# panel.net
KiCad netlist of a schematic drawn in EAGLE
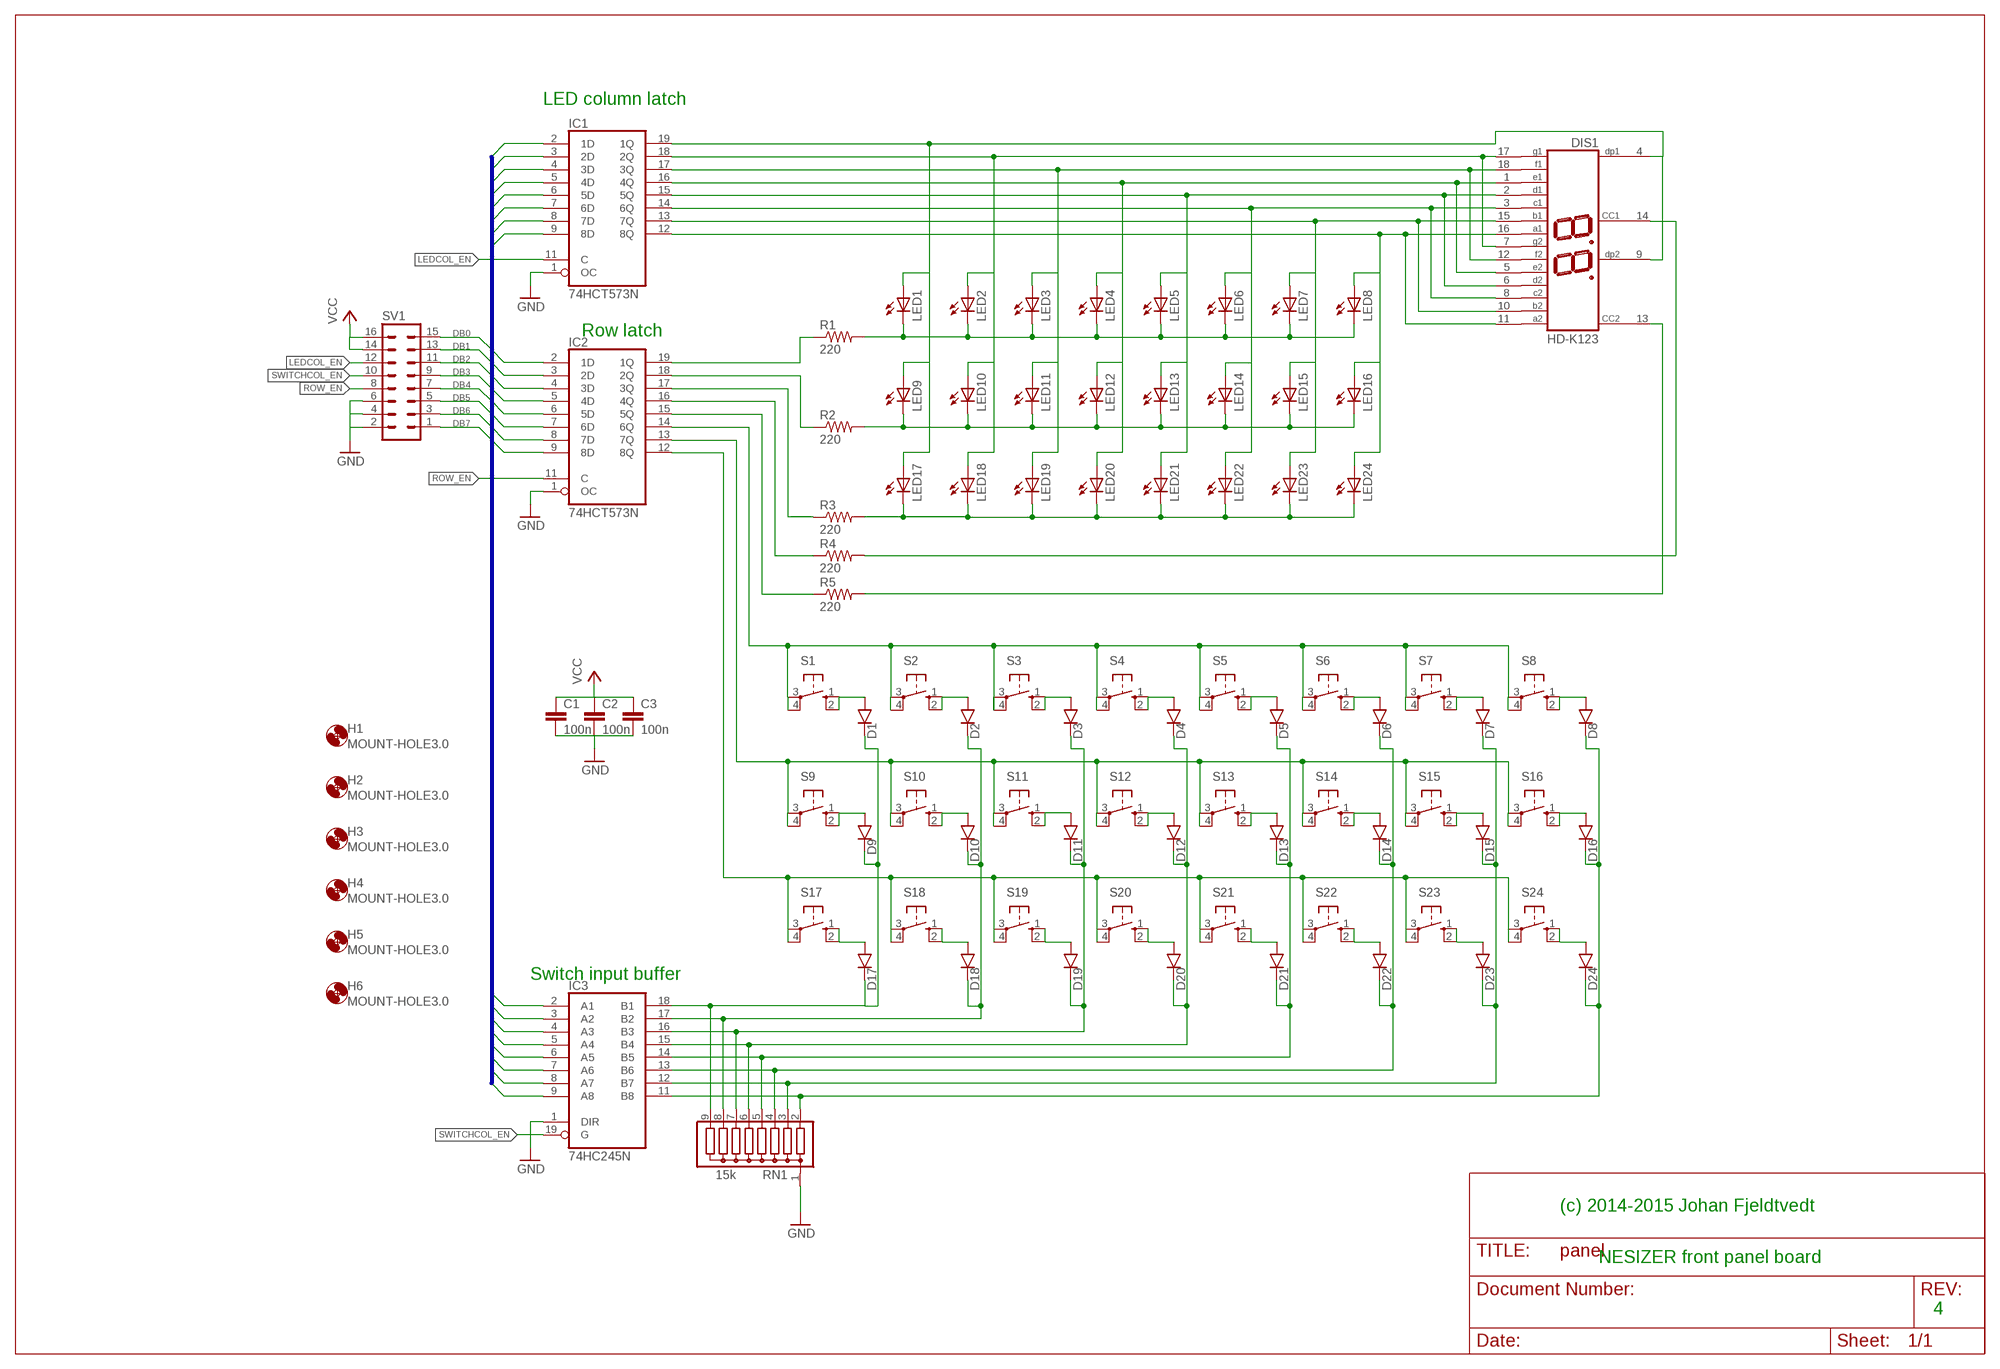
[diagram p0: schematic, sheet 1]

(export (version "E")
  (design (tool "Eeschema 10.0.6"))
  (components
    (comp (ref "C1")
      (value "100n")
      (footprint "eagle-import:C025-025X050")
      (libsource (lib "eagle-import") (part "C-EU025-025X050"))
    )
    (comp (ref "C2")
      (value "100n")
      (footprint "eagle-import:C025-025X050")
      (libsource (lib "eagle-import") (part "C-EU025-025X050"))
    )
    (comp (ref "C3")
      (value "100n")
      (footprint "eagle-import:C025-025X050")
      (libsource (lib "eagle-import") (part "C-EU025-025X050"))
    )
    (comp (ref "D1")
      (value "1N914.3")
      (footprint "eagle-import:DO35-3")
      (libsource (lib "eagle-import") (part "1N914.3"))
    )
    (comp (ref "D2")
      (value "1N914.3")
      (footprint "eagle-import:DO35-3")
      (libsource (lib "eagle-import") (part "1N914.3"))
    )
    (comp (ref "D3")
      (value "1N914.3")
      (footprint "eagle-import:DO35-3")
      (libsource (lib "eagle-import") (part "1N914.3"))
    )
    (comp (ref "D4")
      (value "1N914.3")
      (footprint "eagle-import:DO35-3")
      (libsource (lib "eagle-import") (part "1N914.3"))
    )
    (comp (ref "D5")
      (value "1N914.3")
      (footprint "eagle-import:DO35-3")
      (libsource (lib "eagle-import") (part "1N914.3"))
    )
    (comp (ref "D6")
      (value "1N914.3")
      (footprint "eagle-import:DO35-3")
      (libsource (lib "eagle-import") (part "1N914.3"))
    )
    (comp (ref "D7")
      (value "1N914.3")
      (footprint "eagle-import:DO35-3")
      (libsource (lib "eagle-import") (part "1N914.3"))
    )
    (comp (ref "D8")
      (value "1N914.3")
      (footprint "eagle-import:DO35-3")
      (libsource (lib "eagle-import") (part "1N914.3"))
    )
    (comp (ref "D9")
      (value "1N914.3")
      (footprint "eagle-import:DO35-3")
      (libsource (lib "eagle-import") (part "1N914.3"))
    )
    (comp (ref "D10")
      (value "1N914.3")
      (footprint "eagle-import:DO35-3")
      (libsource (lib "eagle-import") (part "1N914.3"))
    )
    (comp (ref "D11")
      (value "1N914.3")
      (footprint "eagle-import:DO35-3")
      (libsource (lib "eagle-import") (part "1N914.3"))
    )
    (comp (ref "D12")
      (value "1N914.3")
      (footprint "eagle-import:DO35-3")
      (libsource (lib "eagle-import") (part "1N914.3"))
    )
    (comp (ref "D13")
      (value "1N914.3")
      (footprint "eagle-import:DO35-3")
      (libsource (lib "eagle-import") (part "1N914.3"))
    )
    (comp (ref "D14")
      (value "1N914.3")
      (footprint "eagle-import:DO35-3")
      (libsource (lib "eagle-import") (part "1N914.3"))
    )
    (comp (ref "D15")
      (value "1N914.3")
      (footprint "eagle-import:DO35-3")
      (libsource (lib "eagle-import") (part "1N914.3"))
    )
    (comp (ref "D16")
      (value "1N914.3")
      (footprint "eagle-import:DO35-3")
      (libsource (lib "eagle-import") (part "1N914.3"))
    )
    (comp (ref "D17")
      (value "1N914.3")
      (footprint "eagle-import:DO35-3")
      (libsource (lib "eagle-import") (part "1N914.3"))
    )
    (comp (ref "D18")
      (value "1N914.3")
      (footprint "eagle-import:DO35-3")
      (libsource (lib "eagle-import") (part "1N914.3"))
    )
    (comp (ref "D19")
      (value "1N914.3")
      (footprint "eagle-import:DO35-3")
      (libsource (lib "eagle-import") (part "1N914.3"))
    )
    (comp (ref "D20")
      (value "1N914.3")
      (footprint "eagle-import:DO35-3")
      (libsource (lib "eagle-import") (part "1N914.3"))
    )
    (comp (ref "D21")
      (value "1N914.3")
      (footprint "eagle-import:DO35-3")
      (libsource (lib "eagle-import") (part "1N914.3"))
    )
    (comp (ref "D22")
      (value "1N914.3")
      (footprint "eagle-import:DO35-3")
      (libsource (lib "eagle-import") (part "1N914.3"))
    )
    (comp (ref "D23")
      (value "1N914.3")
      (footprint "eagle-import:DO35-3")
      (libsource (lib "eagle-import") (part "1N914.3"))
    )
    (comp (ref "D24")
      (value "1N914.3")
      (footprint "eagle-import:DO35-3")
      (libsource (lib "eagle-import") (part "1N914.3"))
    )
    (comp (ref "DIS1")
      (value "HD-K123")
      (footprint "eagle-import:HDSP-R")
      (libsource (lib "eagle-import") (part "HD-K123"))
    )
    (comp (ref "H1")
      (value "MOUNT-HOLE3.0")
      (footprint "eagle-import:3,0")
      (libsource (lib "eagle-import") (part "MOUNT-HOLE3.0"))
    )
    (comp (ref "H2")
      (value "MOUNT-HOLE3.0")
      (footprint "eagle-import:3,0")
      (libsource (lib "eagle-import") (part "MOUNT-HOLE3.0"))
    )
    (comp (ref "H3")
      (value "MOUNT-HOLE3.0")
      (footprint "eagle-import:3,0")
      (libsource (lib "eagle-import") (part "MOUNT-HOLE3.0"))
    )
    (comp (ref "H4")
      (value "MOUNT-HOLE3.0")
      (footprint "eagle-import:3,0")
      (libsource (lib "eagle-import") (part "MOUNT-HOLE3.0"))
    )
    (comp (ref "H5")
      (value "MOUNT-HOLE3.0")
      (footprint "eagle-import:3,0")
      (libsource (lib "eagle-import") (part "MOUNT-HOLE3.0"))
    )
    (comp (ref "H6")
      (value "MOUNT-HOLE3.0")
      (footprint "eagle-import:3,0")
      (libsource (lib "eagle-import") (part "MOUNT-HOLE3.0"))
    )
    (comp (ref "IC1")
      (value "74HCT573N")
      (footprint "eagle-import:DIL20")
      (libsource (lib "eagle-import") (part "74573NHCT"))
    )
    (comp (ref "IC2")
      (value "74HCT573N")
      (footprint "eagle-import:DIL20")
      (libsource (lib "eagle-import") (part "74573NHCT"))
    )
    (comp (ref "IC3")
      (value "74HC245N")
      (footprint "eagle-import:DIL20")
      (libsource (lib "eagle-import") (part "74245NHC"))
    )
    (comp (ref "LED1")
      (value "LED3MM")
      (footprint "eagle-import:LED3MM")
      (libsource (lib "eagle-import") (part "LED3MM"))
    )
    (comp (ref "LED2")
      (value "LED3MM")
      (footprint "eagle-import:LED3MM")
      (libsource (lib "eagle-import") (part "LED3MM"))
    )
    (comp (ref "LED3")
      (value "LED3MM")
      (footprint "eagle-import:LED3MM")
      (libsource (lib "eagle-import") (part "LED3MM"))
    )
    (comp (ref "LED4")
      (value "LED3MM")
      (footprint "eagle-import:LED3MM")
      (libsource (lib "eagle-import") (part "LED3MM"))
    )
    (comp (ref "LED5")
      (value "LED3MM")
      (footprint "eagle-import:LED3MM")
      (libsource (lib "eagle-import") (part "LED3MM"))
    )
    (comp (ref "LED6")
      (value "LED3MM")
      (footprint "eagle-import:LED3MM")
      (libsource (lib "eagle-import") (part "LED3MM"))
    )
    (comp (ref "LED7")
      (value "LED3MM")
      (footprint "eagle-import:LED3MM")
      (libsource (lib "eagle-import") (part "LED3MM"))
    )
    (comp (ref "LED8")
      (value "LED3MM")
      (footprint "eagle-import:LED3MM")
      (libsource (lib "eagle-import") (part "LED3MM"))
    )
    (comp (ref "LED9")
      (value "LED3MM")
      (footprint "eagle-import:LED3MM")
      (libsource (lib "eagle-import") (part "LED3MM"))
    )
    (comp (ref "LED10")
      (value "LED3MM")
      (footprint "eagle-import:LED3MM")
      (libsource (lib "eagle-import") (part "LED3MM"))
    )
    (comp (ref "LED11")
      (value "LED3MM")
      (footprint "eagle-import:LED3MM")
      (libsource (lib "eagle-import") (part "LED3MM"))
    )
    (comp (ref "LED12")
      (value "LED3MM")
      (footprint "eagle-import:LED3MM")
      (libsource (lib "eagle-import") (part "LED3MM"))
    )
    (comp (ref "LED13")
      (value "LED3MM")
      (footprint "eagle-import:LED3MM")
      (libsource (lib "eagle-import") (part "LED3MM"))
    )
    (comp (ref "LED14")
      (value "LED3MM")
      (footprint "eagle-import:LED3MM")
      (libsource (lib "eagle-import") (part "LED3MM"))
    )
    (comp (ref "LED15")
      (value "LED3MM")
      (footprint "eagle-import:LED3MM")
      (libsource (lib "eagle-import") (part "LED3MM"))
    )
    (comp (ref "LED16")
      (value "LED3MM")
      (footprint "eagle-import:LED3MM")
      (libsource (lib "eagle-import") (part "LED3MM"))
    )
    (comp (ref "LED17")
      (value "LED3MM")
      (footprint "eagle-import:LED3MM")
      (libsource (lib "eagle-import") (part "LED3MM"))
    )
    (comp (ref "LED18")
      (value "LED3MM")
      (footprint "eagle-import:LED3MM")
      (libsource (lib "eagle-import") (part "LED3MM"))
    )
    (comp (ref "LED19")
      (value "LED3MM")
      (footprint "eagle-import:LED3MM")
      (libsource (lib "eagle-import") (part "LED3MM"))
    )
    (comp (ref "LED20")
      (value "LED3MM")
      (footprint "eagle-import:LED3MM")
      (libsource (lib "eagle-import") (part "LED3MM"))
    )
    (comp (ref "LED21")
      (value "LED3MM")
      (footprint "eagle-import:LED3MM")
      (libsource (lib "eagle-import") (part "LED3MM"))
    )
    (comp (ref "LED22")
      (value "LED3MM")
      (footprint "eagle-import:LED3MM")
      (libsource (lib "eagle-import") (part "LED3MM"))
    )
    (comp (ref "LED23")
      (value "LED3MM")
      (footprint "eagle-import:LED3MM")
      (libsource (lib "eagle-import") (part "LED3MM"))
    )
    (comp (ref "LED24")
      (value "LED3MM")
      (footprint "eagle-import:LED3MM")
      (libsource (lib "eagle-import") (part "LED3MM"))
    )
    (comp (ref "R1")
      (value "220")
      (footprint "eagle-import:0207_7")
      (libsource (lib "eagle-import") (part "R-US_0207/7"))
    )
    (comp (ref "R2")
      (value "220")
      (footprint "eagle-import:0207_7")
      (libsource (lib "eagle-import") (part "R-US_0207/7"))
    )
    (comp (ref "R3")
      (value "220")
      (footprint "eagle-import:0207_7")
      (libsource (lib "eagle-import") (part "R-US_0207/7"))
    )
    (comp (ref "R4")
      (value "220")
      (footprint "eagle-import:0207_7")
      (libsource (lib "eagle-import") (part "R-US_0207/7"))
    )
    (comp (ref "R5")
      (value "220")
      (footprint "eagle-import:0207_7")
      (libsource (lib "eagle-import") (part "R-US_0207/7"))
    )
    (comp (ref "RN1")
      (value "15k")
      (footprint "eagle-import:SIL9")
      (libsource (lib "eagle-import") (part "G08R"))
    )
    (comp (ref "S1")
      (value "40-XX")
      (footprint "eagle-import:B3F-40XX")
      (fields (field (name "MF") "OMRON COMPONENTS USA") (field (name "MPN") "B3F-4000"))
      (libsource (lib "eagle-import") (part "40-XX"))
    )
    (comp (ref "S2")
      (value "40-XX")
      (footprint "eagle-import:B3F-40XX")
      (fields (field (name "MF") "OMRON COMPONENTS USA") (field (name "MPN") "B3F-4000"))
      (libsource (lib "eagle-import") (part "40-XX"))
    )
    (comp (ref "S3")
      (value "40-XX")
      (footprint "eagle-import:B3F-40XX")
      (fields (field (name "MF") "OMRON COMPONENTS USA") (field (name "MPN") "B3F-4000"))
      (libsource (lib "eagle-import") (part "40-XX"))
    )
    (comp (ref "S4")
      (value "40-XX")
      (footprint "eagle-import:B3F-40XX")
      (fields (field (name "MF") "OMRON COMPONENTS USA") (field (name "MPN") "B3F-4000"))
      (libsource (lib "eagle-import") (part "40-XX"))
    )
    (comp (ref "S5")
      (value "40-XX")
      (footprint "eagle-import:B3F-40XX")
      (fields (field (name "MF") "OMRON COMPONENTS USA") (field (name "MPN") "B3F-4000"))
      (libsource (lib "eagle-import") (part "40-XX"))
    )
    (comp (ref "S6")
      (value "40-XX")
      (footprint "eagle-import:B3F-40XX")
      (fields (field (name "MF") "OMRON COMPONENTS USA") (field (name "MPN") "B3F-4000"))
      (libsource (lib "eagle-import") (part "40-XX"))
    )
    (comp (ref "S7")
      (value "40-XX")
      (footprint "eagle-import:B3F-40XX")
      (fields (field (name "MF") "OMRON COMPONENTS USA") (field (name "MPN") "B3F-4000"))
      (libsource (lib "eagle-import") (part "40-XX"))
    )
    (comp (ref "S8")
      (value "40-XX")
      (footprint "eagle-import:B3F-40XX")
      (fields (field (name "MF") "OMRON COMPONENTS USA") (field (name "MPN") "B3F-4000"))
      (libsource (lib "eagle-import") (part "40-XX"))
    )
    (comp (ref "S9")
      (value "40-XX")
      (footprint "eagle-import:B3F-40XX")
      (fields (field (name "MF") "OMRON COMPONENTS USA") (field (name "MPN") "B3F-4000"))
      (libsource (lib "eagle-import") (part "40-XX"))
    )
    (comp (ref "S10")
      (value "40-XX")
      (footprint "eagle-import:B3F-40XX")
      (fields (field (name "MF") "OMRON COMPONENTS USA") (field (name "MPN") "B3F-4000"))
      (libsource (lib "eagle-import") (part "40-XX"))
    )
    (comp (ref "S11")
      (value "40-XX")
      (footprint "eagle-import:B3F-40XX")
      (fields (field (name "MF") "OMRON COMPONENTS USA") (field (name "MPN") "B3F-4000"))
      (libsource (lib "eagle-import") (part "40-XX"))
    )
    (comp (ref "S12")
      (value "40-XX")
      (footprint "eagle-import:B3F-40XX")
      (fields (field (name "MF") "OMRON COMPONENTS USA") (field (name "MPN") "B3F-4000"))
      (libsource (lib "eagle-import") (part "40-XX"))
    )
    (comp (ref "S13")
      (value "40-XX")
      (footprint "eagle-import:B3F-40XX")
      (fields (field (name "MF") "OMRON COMPONENTS USA") (field (name "MPN") "B3F-4000"))
      (libsource (lib "eagle-import") (part "40-XX"))
    )
    (comp (ref "S14")
      (value "40-XX")
      (footprint "eagle-import:B3F-40XX")
      (fields (field (name "MF") "OMRON COMPONENTS USA") (field (name "MPN") "B3F-4000"))
      (libsource (lib "eagle-import") (part "40-XX"))
    )
    (comp (ref "S15")
      (value "40-XX")
      (footprint "eagle-import:B3F-40XX")
      (fields (field (name "MF") "OMRON COMPONENTS USA") (field (name "MPN") "B3F-4000"))
      (libsource (lib "eagle-import") (part "40-XX"))
    )
    (comp (ref "S16")
      (value "40-XX")
      (footprint "eagle-import:B3F-40XX")
      (fields (field (name "MF") "OMRON COMPONENTS USA") (field (name "MPN") "B3F-4000"))
      (libsource (lib "eagle-import") (part "40-XX"))
    )
    (comp (ref "S17")
      (value "10-XX")
      (footprint "eagle-import:B3F-10XX")
      (fields (field (name "MPN") "B3F-1000"))
      (libsource (lib "eagle-import") (part "10-XX"))
    )
    (comp (ref "S18")
      (value "10-XX")
      (footprint "eagle-import:B3F-10XX")
      (fields (field (name "MPN") "B3F-1000"))
      (libsource (lib "eagle-import") (part "10-XX"))
    )
    (comp (ref "S19")
      (value "10-XX")
      (footprint "eagle-import:B3F-10XX")
      (fields (field (name "MPN") "B3F-1000"))
      (libsource (lib "eagle-import") (part "10-XX"))
    )
    (comp (ref "S20")
      (value "10-XX")
      (footprint "eagle-import:B3F-10XX")
      (fields (field (name "MPN") "B3F-1000"))
      (libsource (lib "eagle-import") (part "10-XX"))
    )
    (comp (ref "S21")
      (value "10-XX")
      (footprint "eagle-import:B3F-10XX")
      (fields (field (name "MPN") "B3F-1000"))
      (libsource (lib "eagle-import") (part "10-XX"))
    )
    (comp (ref "S22")
      (value "10-XX")
      (footprint "eagle-import:B3F-10XX")
      (fields (field (name "MPN") "B3F-1000"))
      (libsource (lib "eagle-import") (part "10-XX"))
    )
    (comp (ref "S23")
      (value "10-XX")
      (footprint "eagle-import:B3F-10XX")
      (fields (field (name "MPN") "B3F-1000"))
      (libsource (lib "eagle-import") (part "10-XX"))
    )
    (comp (ref "S24")
      (value "10-XX")
      (footprint "eagle-import:B3F-10XX")
      (fields (field (name "MPN") "B3F-1000"))
      (libsource (lib "eagle-import") (part "10-XX"))
    )
    (comp (ref "SV1")
      (value "MA08-2")
      (footprint "eagle-import:MA08-2")
      (libsource (lib "eagle-import") (part "MA08-2"))
    )
  )
  (nets
    (net (code "1") (name "/DB0") (class "Default")
      (node (ref "IC1") (pin "2") (pinfunction "1D_2") (pintype "input"))
      (node (ref "IC2") (pin "2") (pinfunction "1D_2") (pintype "input"))
      (node (ref "IC3") (pin "2") (pinfunction "A1_2") (pintype "bidirectional"))
      (node (ref "SV1") (pin "15") (pinfunction "15_15") (pintype "passive"))
    )
    (net (code "2") (name "/DB1") (class "Default")
      (node (ref "IC1") (pin "3") (pinfunction "2D_3") (pintype "input"))
      (node (ref "IC2") (pin "3") (pinfunction "2D_3") (pintype "input"))
      (node (ref "IC3") (pin "3") (pinfunction "A2_3") (pintype "bidirectional"))
      (node (ref "SV1") (pin "13") (pinfunction "13_13") (pintype "passive"))
    )
    (net (code "3") (name "/DB2") (class "Default")
      (node (ref "IC1") (pin "4") (pinfunction "3D_4") (pintype "input"))
      (node (ref "IC2") (pin "4") (pinfunction "3D_4") (pintype "input"))
      (node (ref "IC3") (pin "4") (pinfunction "A3_4") (pintype "bidirectional"))
      (node (ref "SV1") (pin "11") (pinfunction "11_11") (pintype "passive"))
    )
    (net (code "4") (name "/DB3") (class "Default")
      (node (ref "IC1") (pin "5") (pinfunction "4D_5") (pintype "input"))
      (node (ref "IC2") (pin "5") (pinfunction "4D_5") (pintype "input"))
      (node (ref "IC3") (pin "5") (pinfunction "A4_5") (pintype "bidirectional"))
      (node (ref "SV1") (pin "9") (pinfunction "9_9") (pintype "passive"))
    )
    (net (code "5") (name "/DB4") (class "Default")
      (node (ref "IC1") (pin "6") (pinfunction "5D_6") (pintype "input"))
      (node (ref "IC2") (pin "6") (pinfunction "5D_6") (pintype "input"))
      (node (ref "IC3") (pin "6") (pinfunction "A5_6") (pintype "bidirectional"))
      (node (ref "SV1") (pin "7") (pinfunction "7_7") (pintype "passive"))
    )
    (net (code "6") (name "/DB5") (class "Default")
      (node (ref "IC1") (pin "7") (pinfunction "6D_7") (pintype "input"))
      (node (ref "IC2") (pin "7") (pinfunction "6D_7") (pintype "input"))
      (node (ref "IC3") (pin "7") (pinfunction "A6_7") (pintype "bidirectional"))
      (node (ref "SV1") (pin "5") (pinfunction "5_5") (pintype "passive"))
    )
    (net (code "7") (name "/DB6") (class "Default")
      (node (ref "IC1") (pin "8") (pinfunction "7D_8") (pintype "input"))
      (node (ref "IC2") (pin "8") (pinfunction "7D_8") (pintype "input"))
      (node (ref "IC3") (pin "8") (pinfunction "A7_8") (pintype "bidirectional"))
      (node (ref "SV1") (pin "3") (pinfunction "3_3") (pintype "passive"))
    )
    (net (code "8") (name "/DB7") (class "Default")
      (node (ref "IC1") (pin "9") (pinfunction "8D_9") (pintype "input"))
      (node (ref "IC2") (pin "9") (pinfunction "8D_9") (pintype "input"))
      (node (ref "IC3") (pin "9") (pinfunction "A8_9") (pintype "bidirectional"))
      (node (ref "SV1") (pin "1") (pinfunction "1_1") (pintype "passive"))
    )
    (net (code "9") (name "GND") (class "Default")
      (node (ref "C1") (pin "2") (pinfunction "2_2") (pintype "passive"))
      (node (ref "C2") (pin "2") (pinfunction "2_2") (pintype "passive"))
      (node (ref "C3") (pin "2") (pinfunction "2_2") (pintype "passive"))
      (node (ref "IC1") (pin "1") (pinfunction "OC_1") (pintype "input"))
      (node (ref "IC2") (pin "1") (pinfunction "OC_1") (pintype "input"))
      (node (ref "IC3") (pin "1") (pinfunction "DIR_1") (pintype "input"))
      (node (ref "RN1") (pin "1") (pinfunction "1_1") (pintype "passive"))
      (node (ref "SV1") (pin "2") (pinfunction "2_2") (pintype "passive"))
      (node (ref "SV1") (pin "4") (pinfunction "4_4") (pintype "passive"))
      (node (ref "SV1") (pin "6") (pinfunction "6_6") (pintype "passive"))
    )
    (net (code "10") (name "LEDCOL_EN") (class "Default")
      (node (ref "IC1") (pin "11") (pinfunction "C_11") (pintype "input"))
      (node (ref "SV1") (pin "12") (pinfunction "12_12") (pintype "passive"))
    )
    (net (code "11") (name "Net-(DIS1-A1)") (class "Default")
      (node (ref "DIS1") (pin "11") (pinfunction "A2_11") (pintype "passive"))
      (node (ref "DIS1") (pin "16") (pinfunction "A1_16") (pintype "passive"))
      (node (ref "IC1") (pin "12") (pinfunction "8Q_12") (pintype "tri_state"))
      (node (ref "LED16") (pin "A") (pinfunction "A_A") (pintype "passive"))
      (node (ref "LED24") (pin "A") (pinfunction "A_A") (pintype "passive"))
      (node (ref "LED8") (pin "A") (pinfunction "A_A") (pintype "passive"))
    )
    (net (code "12") (name "Net-(DIS1-B1)") (class "Default")
      (node (ref "DIS1") (pin "10") (pinfunction "B2_10") (pintype "passive"))
      (node (ref "DIS1") (pin "15") (pinfunction "B1_15") (pintype "passive"))
      (node (ref "IC1") (pin "13") (pinfunction "7Q_13") (pintype "tri_state"))
      (node (ref "LED15") (pin "A") (pinfunction "A_A") (pintype "passive"))
      (node (ref "LED23") (pin "A") (pinfunction "A_A") (pintype "passive"))
      (node (ref "LED7") (pin "A") (pinfunction "A_A") (pintype "passive"))
    )
    (net (code "13") (name "Net-(DIS1-C1)") (class "Default")
      (node (ref "DIS1") (pin "3") (pinfunction "C1_3") (pintype "passive"))
      (node (ref "DIS1") (pin "8") (pinfunction "C2_8") (pintype "passive"))
      (node (ref "IC1") (pin "14") (pinfunction "6Q_14") (pintype "tri_state"))
      (node (ref "LED14") (pin "A") (pinfunction "A_A") (pintype "passive"))
      (node (ref "LED22") (pin "A") (pinfunction "A_A") (pintype "passive"))
      (node (ref "LED6") (pin "A") (pinfunction "A_A") (pintype "passive"))
    )
    (net (code "14") (name "Net-(DIS1-CC1)") (class "Default")
      (node (ref "DIS1") (pin "14") (pinfunction "CC1_14") (pintype "passive"))
      (node (ref "R4") (pin "2") (pinfunction "2_2") (pintype "passive"))
    )
    (net (code "15") (name "Net-(DIS1-CC2)") (class "Default")
      (node (ref "DIS1") (pin "13") (pinfunction "CC2_13") (pintype "passive"))
      (node (ref "R5") (pin "2") (pinfunction "2_2") (pintype "passive"))
    )
    (net (code "16") (name "Net-(DIS1-D1)") (class "Default")
      (node (ref "DIS1") (pin "2") (pinfunction "D1_2") (pintype "passive"))
      (node (ref "DIS1") (pin "6") (pinfunction "D2_6") (pintype "passive"))
      (node (ref "IC1") (pin "15") (pinfunction "5Q_15") (pintype "tri_state"))
      (node (ref "LED13") (pin "A") (pinfunction "A_A") (pintype "passive"))
      (node (ref "LED21") (pin "A") (pinfunction "A_A") (pintype "passive"))
      (node (ref "LED5") (pin "A") (pinfunction "A_A") (pintype "passive"))
    )
    (net (code "17") (name "Net-(DIS1-DP1)") (class "Default")
      (node (ref "DIS1") (pin "4") (pinfunction "DP1_4") (pintype "passive"))
      (node (ref "DIS1") (pin "9") (pinfunction "DP2_9") (pintype "passive"))
      (node (ref "IC1") (pin "19") (pinfunction "1Q_19") (pintype "tri_state"))
      (node (ref "LED1") (pin "A") (pinfunction "A_A") (pintype "passive"))
      (node (ref "LED17") (pin "A") (pinfunction "A_A") (pintype "passive"))
      (node (ref "LED9") (pin "A") (pinfunction "A_A") (pintype "passive"))
    )
    (net (code "18") (name "Net-(DIS1-E1)") (class "Default")
      (node (ref "DIS1") (pin "1") (pinfunction "E1_1") (pintype "passive"))
      (node (ref "DIS1") (pin "5") (pinfunction "E2_5") (pintype "passive"))
      (node (ref "IC1") (pin "16") (pinfunction "4Q_16") (pintype "tri_state"))
      (node (ref "LED12") (pin "A") (pinfunction "A_A") (pintype "passive"))
      (node (ref "LED20") (pin "A") (pinfunction "A_A") (pintype "passive"))
      (node (ref "LED4") (pin "A") (pinfunction "A_A") (pintype "passive"))
    )
    (net (code "19") (name "Net-(DIS1-F1)") (class "Default")
      (node (ref "DIS1") (pin "12") (pinfunction "F2_12") (pintype "passive"))
      (node (ref "DIS1") (pin "18") (pinfunction "F1_18") (pintype "passive"))
      (node (ref "IC1") (pin "17") (pinfunction "3Q_17") (pintype "tri_state"))
      (node (ref "LED11") (pin "A") (pinfunction "A_A") (pintype "passive"))
      (node (ref "LED19") (pin "A") (pinfunction "A_A") (pintype "passive"))
      (node (ref "LED3") (pin "A") (pinfunction "A_A") (pintype "passive"))
    )
    (net (code "20") (name "Net-(DIS1-G1)") (class "Default")
      (node (ref "DIS1") (pin "17") (pinfunction "G1_17") (pintype "passive"))
      (node (ref "DIS1") (pin "7") (pinfunction "G2_7") (pintype "passive"))
      (node (ref "IC1") (pin "18") (pinfunction "2Q_18") (pintype "tri_state"))
      (node (ref "LED10") (pin "A") (pinfunction "A_A") (pintype "passive"))
      (node (ref "LED18") (pin "A") (pinfunction "A_A") (pintype "passive"))
      (node (ref "LED2") (pin "A") (pinfunction "A_A") (pintype "passive"))
    )
    (net (code "21") (name "Net-(IC2A-1Q)") (class "Default")
      (node (ref "IC2") (pin "19") (pinfunction "1Q_19") (pintype "tri_state"))
      (node (ref "R1") (pin "1") (pinfunction "1_1") (pintype "passive"))
    )
    (net (code "22") (name "Net-(IC2A-2Q)") (class "Default")
      (node (ref "IC2") (pin "18") (pinfunction "2Q_18") (pintype "tri_state"))
      (node (ref "R2") (pin "1") (pinfunction "1_1") (pintype "passive"))
    )
    (net (code "23") (name "Net-(IC2A-3Q)") (class "Default")
      (node (ref "IC2") (pin "17") (pinfunction "3Q_17") (pintype "tri_state"))
      (node (ref "R3") (pin "1") (pinfunction "1_1") (pintype "passive"))
    )
    (net (code "24") (name "Net-(IC2A-4Q)") (class "Default")
      (node (ref "IC2") (pin "16") (pinfunction "4Q_16") (pintype "tri_state"))
      (node (ref "R4") (pin "1") (pinfunction "1_1") (pintype "passive"))
    )
    (net (code "25") (name "Net-(IC2A-5Q)") (class "Default")
      (node (ref "IC2") (pin "15") (pinfunction "5Q_15") (pintype "tri_state"))
      (node (ref "R5") (pin "1") (pinfunction "1_1") (pintype "passive"))
    )
    (net (code "26") (name "Net-(IC2A-6Q)") (class "Default")
      (node (ref "IC2") (pin "14") (pinfunction "6Q_14") (pintype "tri_state"))
      (node (ref "S1") (pin "3") (pinfunction "P_3") (pintype "passive"))
      (node (ref "S1") (pin "4") (pinfunction "P1_4") (pintype "passive"))
      (node (ref "S2") (pin "3") (pinfunction "P_3") (pintype "passive"))
      (node (ref "S2") (pin "4") (pinfunction "P1_4") (pintype "passive"))
      (node (ref "S3") (pin "3") (pinfunction "P_3") (pintype "passive"))
      (node (ref "S3") (pin "4") (pinfunction "P1_4") (pintype "passive"))
      (node (ref "S4") (pin "3") (pinfunction "P_3") (pintype "passive"))
      (node (ref "S4") (pin "4") (pinfunction "P1_4") (pintype "passive"))
      (node (ref "S5") (pin "3") (pinfunction "P_3") (pintype "passive"))
      (node (ref "S5") (pin "4") (pinfunction "P1_4") (pintype "passive"))
      (node (ref "S6") (pin "3") (pinfunction "P_3") (pintype "passive"))
      (node (ref "S6") (pin "4") (pinfunction "P1_4") (pintype "passive"))
      (node (ref "S7") (pin "3") (pinfunction "P_3") (pintype "passive"))
      (node (ref "S7") (pin "4") (pinfunction "P1_4") (pintype "passive"))
      (node (ref "S8") (pin "3") (pinfunction "P_3") (pintype "passive"))
      (node (ref "S8") (pin "4") (pinfunction "P1_4") (pintype "passive"))
    )
    (net (code "27") (name "Net-(IC2A-7Q)") (class "Default")
      (node (ref "IC2") (pin "13") (pinfunction "7Q_13") (pintype "tri_state"))
      (node (ref "S10") (pin "3") (pinfunction "P_3") (pintype "passive"))
      (node (ref "S10") (pin "4") (pinfunction "P1_4") (pintype "passive"))
      (node (ref "S11") (pin "3") (pinfunction "P_3") (pintype "passive"))
      (node (ref "S11") (pin "4") (pinfunction "P1_4") (pintype "passive"))
      (node (ref "S12") (pin "3") (pinfunction "P_3") (pintype "passive"))
      (node (ref "S12") (pin "4") (pinfunction "P1_4") (pintype "passive"))
      (node (ref "S13") (pin "3") (pinfunction "P_3") (pintype "passive"))
      (node (ref "S13") (pin "4") (pinfunction "P1_4") (pintype "passive"))
      (node (ref "S14") (pin "3") (pinfunction "P_3") (pintype "passive"))
      (node (ref "S14") (pin "4") (pinfunction "P1_4") (pintype "passive"))
      (node (ref "S15") (pin "3") (pinfunction "P_3") (pintype "passive"))
      (node (ref "S15") (pin "4") (pinfunction "P1_4") (pintype "passive"))
      (node (ref "S16") (pin "3") (pinfunction "P_3") (pintype "passive"))
      (node (ref "S16") (pin "4") (pinfunction "P1_4") (pintype "passive"))
      (node (ref "S9") (pin "3") (pinfunction "P_3") (pintype "passive"))
      (node (ref "S9") (pin "4") (pinfunction "P1_4") (pintype "passive"))
    )
    (net (code "28") (name "Net-(IC2A-8Q)") (class "Default")
      (node (ref "IC2") (pin "12") (pinfunction "8Q_12") (pintype "tri_state"))
      (node (ref "S17") (pin "3") (pinfunction "P_3") (pintype "passive"))
      (node (ref "S17") (pin "4") (pinfunction "P1_4") (pintype "passive"))
      (node (ref "S18") (pin "3") (pinfunction "P_3") (pintype "passive"))
      (node (ref "S18") (pin "4") (pinfunction "P1_4") (pintype "passive"))
      (node (ref "S19") (pin "3") (pinfunction "P_3") (pintype "passive"))
      (node (ref "S19") (pin "4") (pinfunction "P1_4") (pintype "passive"))
      (node (ref "S20") (pin "3") (pinfunction "P_3") (pintype "passive"))
      (node (ref "S20") (pin "4") (pinfunction "P1_4") (pintype "passive"))
      (node (ref "S21") (pin "3") (pinfunction "P_3") (pintype "passive"))
      (node (ref "S21") (pin "4") (pinfunction "P1_4") (pintype "passive"))
      (node (ref "S22") (pin "3") (pinfunction "P_3") (pintype "passive"))
      (node (ref "S22") (pin "4") (pinfunction "P1_4") (pintype "passive"))
      (node (ref "S23") (pin "3") (pinfunction "P_3") (pintype "passive"))
      (node (ref "S23") (pin "4") (pinfunction "P1_4") (pintype "passive"))
      (node (ref "S24") (pin "3") (pinfunction "P_3") (pintype "passive"))
      (node (ref "S24") (pin "4") (pinfunction "P1_4") (pintype "passive"))
    )
    (net (code "29") (name "Net-(IC3A-B1)") (class "Default")
      (node (ref "D1") (pin "C") (pinfunction "C_C") (pintype "passive"))
      (node (ref "D17") (pin "C") (pinfunction "C_C") (pintype "passive"))
      (node (ref "D9") (pin "C") (pinfunction "C_C") (pintype "passive"))
      (node (ref "IC3") (pin "18") (pinfunction "B1_18") (pintype "bidirectional"))
      (node (ref "RN1") (pin "9") (pinfunction "9_9") (pintype "passive"))
    )
    (net (code "30") (name "Net-(IC3A-B2)") (class "Default")
      (node (ref "D10") (pin "C") (pinfunction "C_C") (pintype "passive"))
      (node (ref "D18") (pin "C") (pinfunction "C_C") (pintype "passive"))
      (node (ref "D2") (pin "C") (pinfunction "C_C") (pintype "passive"))
      (node (ref "IC3") (pin "17") (pinfunction "B2_17") (pintype "bidirectional"))
      (node (ref "RN1") (pin "8") (pinfunction "8_8") (pintype "passive"))
    )
    (net (code "31") (name "Net-(IC3A-B3)") (class "Default")
      (node (ref "D11") (pin "C") (pinfunction "C_C") (pintype "passive"))
      (node (ref "D19") (pin "C") (pinfunction "C_C") (pintype "passive"))
      (node (ref "D3") (pin "C") (pinfunction "C_C") (pintype "passive"))
      (node (ref "IC3") (pin "16") (pinfunction "B3_16") (pintype "bidirectional"))
      (node (ref "RN1") (pin "7") (pinfunction "7_7") (pintype "passive"))
    )
    (net (code "32") (name "Net-(IC3A-B4)") (class "Default")
      (node (ref "D12") (pin "C") (pinfunction "C_C") (pintype "passive"))
      (node (ref "D20") (pin "C") (pinfunction "C_C") (pintype "passive"))
      (node (ref "D4") (pin "C") (pinfunction "C_C") (pintype "passive"))
      (node (ref "IC3") (pin "15") (pinfunction "B4_15") (pintype "bidirectional"))
      (node (ref "RN1") (pin "6") (pinfunction "6_6") (pintype "passive"))
    )
    (net (code "33") (name "Net-(IC3A-B5)") (class "Default")
      (node (ref "D13") (pin "C") (pinfunction "C_C") (pintype "passive"))
      (node (ref "D21") (pin "C") (pinfunction "C_C") (pintype "passive"))
      (node (ref "D5") (pin "C") (pinfunction "C_C") (pintype "passive"))
      (node (ref "IC3") (pin "14") (pinfunction "B5_14") (pintype "bidirectional"))
      (node (ref "RN1") (pin "5") (pinfunction "5_5") (pintype "passive"))
    )
    (net (code "34") (name "Net-(IC3A-B6)") (class "Default")
      (node (ref "D14") (pin "C") (pinfunction "C_C") (pintype "passive"))
      (node (ref "D22") (pin "C") (pinfunction "C_C") (pintype "passive"))
      (node (ref "D6") (pin "C") (pinfunction "C_C") (pintype "passive"))
      (node (ref "IC3") (pin "13") (pinfunction "B6_13") (pintype "bidirectional"))
      (node (ref "RN1") (pin "4") (pinfunction "4_4") (pintype "passive"))
    )
    (net (code "35") (name "Net-(IC3A-B7)") (class "Default")
      (node (ref "D15") (pin "C") (pinfunction "C_C") (pintype "passive"))
      (node (ref "D23") (pin "C") (pinfunction "C_C") (pintype "passive"))
      (node (ref "D7") (pin "C") (pinfunction "C_C") (pintype "passive"))
      (node (ref "IC3") (pin "12") (pinfunction "B7_12") (pintype "bidirectional"))
      (node (ref "RN1") (pin "3") (pinfunction "3_3") (pintype "passive"))
    )
    (net (code "36") (name "Net-(IC3A-B8)") (class "Default")
      (node (ref "D16") (pin "C") (pinfunction "C_C") (pintype "passive"))
      (node (ref "D24") (pin "C") (pinfunction "C_C") (pintype "passive"))
      (node (ref "D8") (pin "C") (pinfunction "C_C") (pintype "passive"))
      (node (ref "IC3") (pin "11") (pinfunction "B8_11") (pintype "bidirectional"))
      (node (ref "RN1") (pin "2") (pinfunction "2_2") (pintype "passive"))
    )
    (net (code "37") (name "Net-(LED1-C)") (class "Default")
      (node (ref "LED1") (pin "K") (pinfunction "C_K") (pintype "passive"))
      (node (ref "LED2") (pin "K") (pinfunction "C_K") (pintype "passive"))
      (node (ref "LED3") (pin "K") (pinfunction "C_K") (pintype "passive"))
      (node (ref "LED4") (pin "K") (pinfunction "C_K") (pintype "passive"))
      (node (ref "LED5") (pin "K") (pinfunction "C_K") (pintype "passive"))
      (node (ref "LED6") (pin "K") (pinfunction "C_K") (pintype "passive"))
      (node (ref "LED7") (pin "K") (pinfunction "C_K") (pintype "passive"))
      (node (ref "LED8") (pin "K") (pinfunction "C_K") (pintype "passive"))
      (node (ref "R1") (pin "2") (pinfunction "2_2") (pintype "passive"))
    )
    (net (code "38") (name "Net-(LED10-C)") (class "Default")
      (node (ref "LED10") (pin "K") (pinfunction "C_K") (pintype "passive"))
      (node (ref "LED11") (pin "K") (pinfunction "C_K") (pintype "passive"))
      (node (ref "LED12") (pin "K") (pinfunction "C_K") (pintype "passive"))
      (node (ref "LED13") (pin "K") (pinfunction "C_K") (pintype "passive"))
      (node (ref "LED14") (pin "K") (pinfunction "C_K") (pintype "passive"))
      (node (ref "LED15") (pin "K") (pinfunction "C_K") (pintype "passive"))
      (node (ref "LED16") (pin "K") (pinfunction "C_K") (pintype "passive"))
      (node (ref "LED9") (pin "K") (pinfunction "C_K") (pintype "passive"))
      (node (ref "R2") (pin "2") (pinfunction "2_2") (pintype "passive"))
    )
    (net (code "39") (name "Net-(LED17-C)") (class "Default")
      (node (ref "LED17") (pin "K") (pinfunction "C_K") (pintype "passive"))
      (node (ref "LED18") (pin "K") (pinfunction "C_K") (pintype "passive"))
      (node (ref "LED19") (pin "K") (pinfunction "C_K") (pintype "passive"))
      (node (ref "LED20") (pin "K") (pinfunction "C_K") (pintype "passive"))
      (node (ref "LED21") (pin "K") (pinfunction "C_K") (pintype "passive"))
      (node (ref "LED22") (pin "K") (pinfunction "C_K") (pintype "passive"))
      (node (ref "LED23") (pin "K") (pinfunction "C_K") (pintype "passive"))
      (node (ref "LED24") (pin "K") (pinfunction "C_K") (pintype "passive"))
      (node (ref "R3") (pin "2") (pinfunction "2_2") (pintype "passive"))
    )
    (net (code "40") (name "Net-(S1-S)") (class "Default")
      (node (ref "D1") (pin "A") (pinfunction "A_A") (pintype "passive"))
      (node (ref "S1") (pin "1") (pinfunction "S_1") (pintype "passive"))
      (node (ref "S1") (pin "2") (pinfunction "S1_2") (pintype "passive"))
    )
    (net (code "41") (name "Net-(S2-S)") (class "Default")
      (node (ref "D2") (pin "A") (pinfunction "A_A") (pintype "passive"))
      (node (ref "S2") (pin "1") (pinfunction "S_1") (pintype "passive"))
      (node (ref "S2") (pin "2") (pinfunction "S1_2") (pintype "passive"))
    )
    (net (code "42") (name "Net-(S3-S)") (class "Default")
      (node (ref "D3") (pin "A") (pinfunction "A_A") (pintype "passive"))
      (node (ref "S3") (pin "1") (pinfunction "S_1") (pintype "passive"))
      (node (ref "S3") (pin "2") (pinfunction "S1_2") (pintype "passive"))
    )
    (net (code "43") (name "Net-(S4-S)") (class "Default")
      (node (ref "D4") (pin "A") (pinfunction "A_A") (pintype "passive"))
      (node (ref "S4") (pin "1") (pinfunction "S_1") (pintype "passive"))
      (node (ref "S4") (pin "2") (pinfunction "S1_2") (pintype "passive"))
    )
    (net (code "44") (name "Net-(S5-S)") (class "Default")
      (node (ref "D5") (pin "A") (pinfunction "A_A") (pintype "passive"))
      (node (ref "S5") (pin "1") (pinfunction "S_1") (pintype "passive"))
      (node (ref "S5") (pin "2") (pinfunction "S1_2") (pintype "passive"))
    )
    (net (code "45") (name "Net-(S6-S)") (class "Default")
      (node (ref "D6") (pin "A") (pinfunction "A_A") (pintype "passive"))
      (node (ref "S6") (pin "1") (pinfunction "S_1") (pintype "passive"))
      (node (ref "S6") (pin "2") (pinfunction "S1_2") (pintype "passive"))
    )
    (net (code "46") (name "Net-(S7-S)") (class "Default")
      (node (ref "D7") (pin "A") (pinfunction "A_A") (pintype "passive"))
      (node (ref "S7") (pin "1") (pinfunction "S_1") (pintype "passive"))
      (node (ref "S7") (pin "2") (pinfunction "S1_2") (pintype "passive"))
    )
    (net (code "47") (name "Net-(S8-S)") (class "Default")
      (node (ref "D8") (pin "A") (pinfunction "A_A") (pintype "passive"))
      (node (ref "S8") (pin "1") (pinfunction "S_1") (pintype "passive"))
      (node (ref "S8") (pin "2") (pinfunction "S1_2") (pintype "passive"))
    )
    (net (code "48") (name "Net-(S9-S)") (class "Default")
      (node (ref "D9") (pin "A") (pinfunction "A_A") (pintype "passive"))
      (node (ref "S9") (pin "1") (pinfunction "S_1") (pintype "passive"))
      (node (ref "S9") (pin "2") (pinfunction "S1_2") (pintype "passive"))
    )
    (net (code "49") (name "Net-(S10-S)") (class "Default")
      (node (ref "D10") (pin "A") (pinfunction "A_A") (pintype "passive"))
      (node (ref "S10") (pin "1") (pinfunction "S_1") (pintype "passive"))
      (node (ref "S10") (pin "2") (pinfunction "S1_2") (pintype "passive"))
    )
    (net (code "50") (name "Net-(S11-S)") (class "Default")
      (node (ref "D11") (pin "A") (pinfunction "A_A") (pintype "passive"))
      (node (ref "S11") (pin "1") (pinfunction "S_1") (pintype "passive"))
      (node (ref "S11") (pin "2") (pinfunction "S1_2") (pintype "passive"))
    )
    (net (code "51") (name "Net-(S12-S)") (class "Default")
      (node (ref "D12") (pin "A") (pinfunction "A_A") (pintype "passive"))
      (node (ref "S12") (pin "1") (pinfunction "S_1") (pintype "passive"))
      (node (ref "S12") (pin "2") (pinfunction "S1_2") (pintype "passive"))
    )
    (net (code "52") (name "Net-(S13-S)") (class "Default")
      (node (ref "D13") (pin "A") (pinfunction "A_A") (pintype "passive"))
      (node (ref "S13") (pin "1") (pinfunction "S_1") (pintype "passive"))
      (node (ref "S13") (pin "2") (pinfunction "S1_2") (pintype "passive"))
    )
    (net (code "53") (name "Net-(S14-S)") (class "Default")
      (node (ref "D14") (pin "A") (pinfunction "A_A") (pintype "passive"))
      (node (ref "S14") (pin "1") (pinfunction "S_1") (pintype "passive"))
      (node (ref "S14") (pin "2") (pinfunction "S1_2") (pintype "passive"))
    )
    (net (code "54") (name "Net-(S15-S)") (class "Default")
      (node (ref "D15") (pin "A") (pinfunction "A_A") (pintype "passive"))
      (node (ref "S15") (pin "1") (pinfunction "S_1") (pintype "passive"))
      (node (ref "S15") (pin "2") (pinfunction "S1_2") (pintype "passive"))
    )
    (net (code "55") (name "Net-(S16-S)") (class "Default")
      (node (ref "D16") (pin "A") (pinfunction "A_A") (pintype "passive"))
      (node (ref "S16") (pin "1") (pinfunction "S_1") (pintype "passive"))
      (node (ref "S16") (pin "2") (pinfunction "S1_2") (pintype "passive"))
    )
    (net (code "56") (name "Net-(S17-S)") (class "Default")
      (node (ref "D17") (pin "A") (pinfunction "A_A") (pintype "passive"))
      (node (ref "S17") (pin "1") (pinfunction "S_1") (pintype "passive"))
      (node (ref "S17") (pin "2") (pinfunction "S1_2") (pintype "passive"))
    )
    (net (code "57") (name "Net-(S18-S)") (class "Default")
      (node (ref "D18") (pin "A") (pinfunction "A_A") (pintype "passive"))
      (node (ref "S18") (pin "1") (pinfunction "S_1") (pintype "passive"))
      (node (ref "S18") (pin "2") (pinfunction "S1_2") (pintype "passive"))
    )
    (net (code "58") (name "Net-(S19-S)") (class "Default")
      (node (ref "D19") (pin "A") (pinfunction "A_A") (pintype "passive"))
      (node (ref "S19") (pin "1") (pinfunction "S_1") (pintype "passive"))
      (node (ref "S19") (pin "2") (pinfunction "S1_2") (pintype "passive"))
    )
    (net (code "59") (name "Net-(S20-S)") (class "Default")
      (node (ref "D20") (pin "A") (pinfunction "A_A") (pintype "passive"))
      (node (ref "S20") (pin "1") (pinfunction "S_1") (pintype "passive"))
      (node (ref "S20") (pin "2") (pinfunction "S1_2") (pintype "passive"))
    )
    (net (code "60") (name "Net-(S21-S)") (class "Default")
      (node (ref "D21") (pin "A") (pinfunction "A_A") (pintype "passive"))
      (node (ref "S21") (pin "1") (pinfunction "S_1") (pintype "passive"))
      (node (ref "S21") (pin "2") (pinfunction "S1_2") (pintype "passive"))
    )
    (net (code "61") (name "Net-(S22-S)") (class "Default")
      (node (ref "D22") (pin "A") (pinfunction "A_A") (pintype "passive"))
      (node (ref "S22") (pin "1") (pinfunction "S_1") (pintype "passive"))
      (node (ref "S22") (pin "2") (pinfunction "S1_2") (pintype "passive"))
    )
    (net (code "62") (name "Net-(S23-S)") (class "Default")
      (node (ref "D23") (pin "A") (pinfunction "A_A") (pintype "passive"))
      (node (ref "S23") (pin "1") (pinfunction "S_1") (pintype "passive"))
      (node (ref "S23") (pin "2") (pinfunction "S1_2") (pintype "passive"))
    )
    (net (code "63") (name "Net-(S24-S)") (class "Default")
      (node (ref "D24") (pin "A") (pinfunction "A_A") (pintype "passive"))
      (node (ref "S24") (pin "1") (pinfunction "S_1") (pintype "passive"))
      (node (ref "S24") (pin "2") (pinfunction "S1_2") (pintype "passive"))
    )
    (net (code "64") (name "ROW_EN") (class "Default")
      (node (ref "IC2") (pin "11") (pinfunction "C_11") (pintype "input"))
      (node (ref "SV1") (pin "8") (pinfunction "8_8") (pintype "passive"))
    )
    (net (code "65") (name "SWITCHCOL_EN") (class "Default")
      (node (ref "IC3") (pin "19") (pinfunction "G_19") (pintype "input"))
      (node (ref "SV1") (pin "10") (pinfunction "10_10") (pintype "passive"))
    )
    (net (code "66") (name "VCC") (class "Default")
      (node (ref "C1") (pin "1") (pinfunction "1_1") (pintype "passive"))
      (node (ref "C2") (pin "1") (pinfunction "1_1") (pintype "passive"))
      (node (ref "C3") (pin "1") (pinfunction "1_1") (pintype "passive"))
      (node (ref "SV1") (pin "14") (pinfunction "14_14") (pintype "passive"))
      (node (ref "SV1") (pin "16") (pinfunction "16_16") (pintype "passive"))
    )
  )
)
